# Teensy3_based_M_M_board_Autorouted.net
KiCad netlist of a schematic drawn in EAGLE
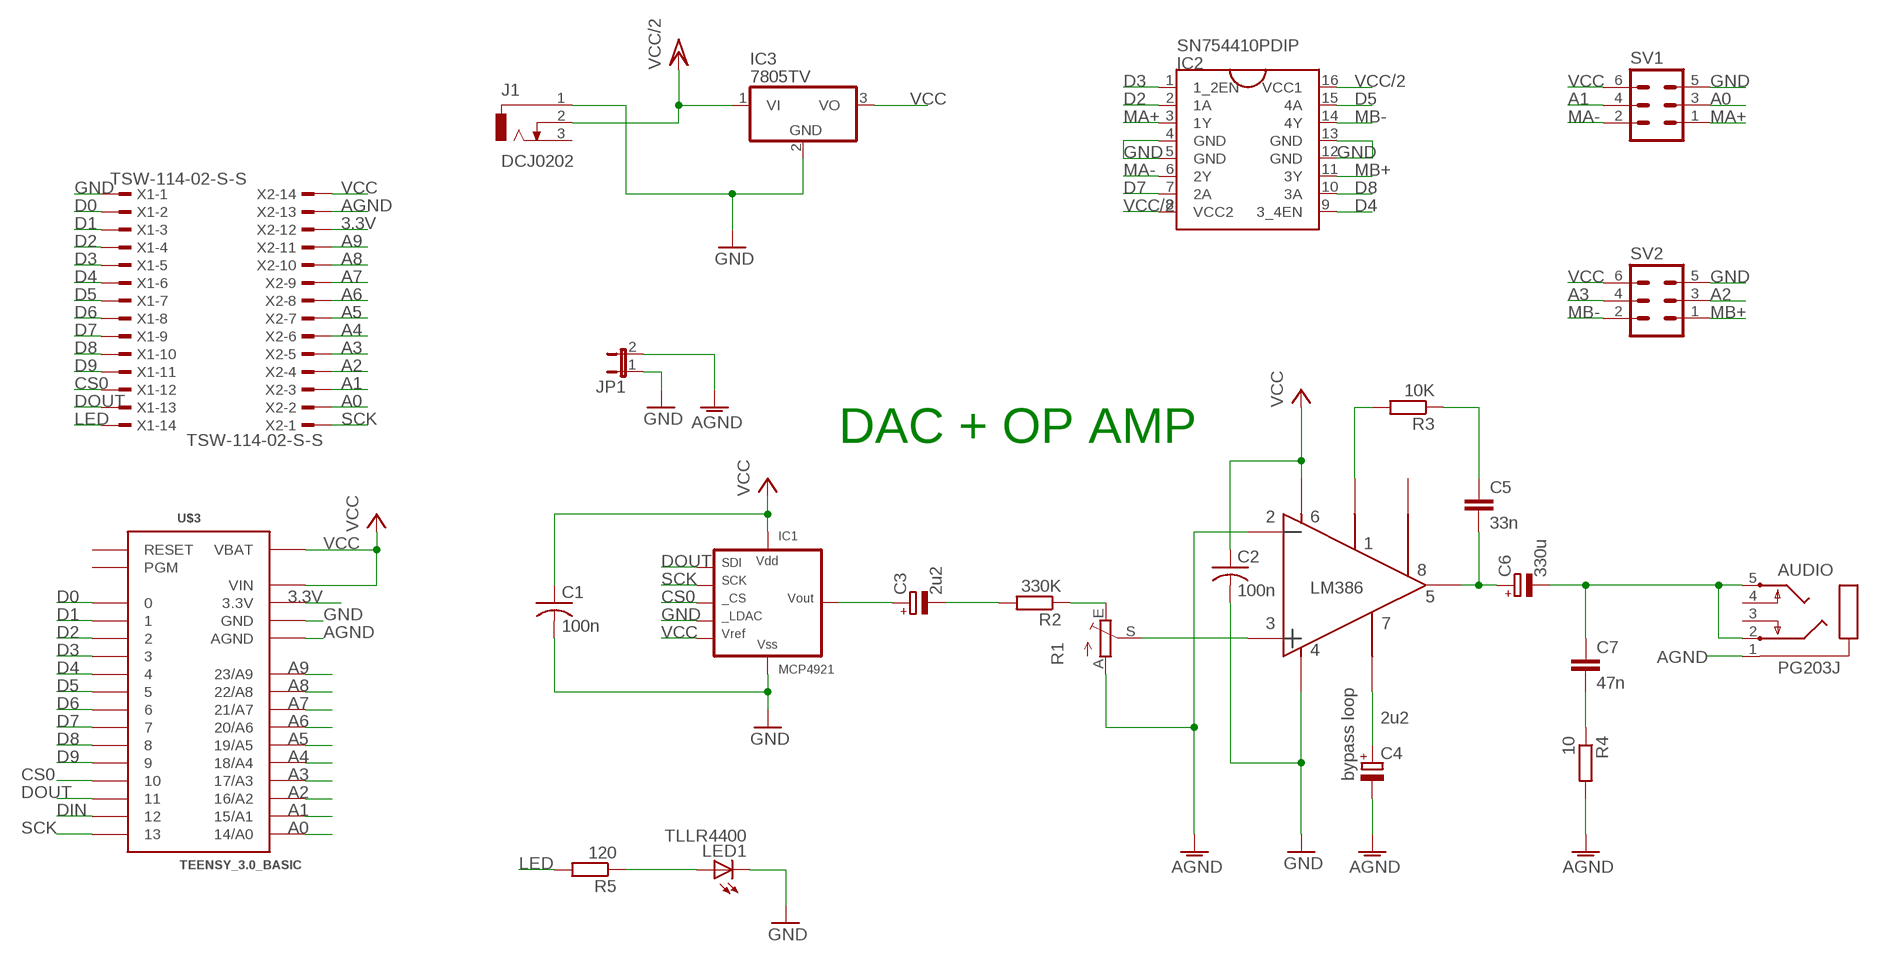
[diagram p0: schematic, sheet 1]

(export (version "E")
  (design (tool "Eeschema 10.0.6"))
  (components
    (comp (ref "AUDIO")
      (value "PG203J")
      (footprint "eagle-import:PG203J")
      (libsource (lib "eagle-import") (part "PG203J"))
    )
    (comp (ref "C1")
      (value "100n")
      (footprint "eagle-import:C050-035X075")
      (libsource (lib "eagle-import") (part "C-US050-035X075"))
    )
    (comp (ref "C2")
      (value "100n")
      (footprint "eagle-import:C050-035X075")
      (libsource (lib "eagle-import") (part "C-US050-035X075"))
    )
    (comp (ref "C3")
      (value "2u2")
      (footprint "eagle-import:E2-5")
      (libsource (lib "eagle-import") (part "CPOL-EUE2-5"))
    )
    (comp (ref "C4")
      (value "2u2")
      (footprint "eagle-import:E2-5")
      (libsource (lib "eagle-import") (part "CPOL-EUE2-5"))
    )
    (comp (ref "C5")
      (value "33n")
      (footprint "eagle-import:C050-024X044")
      (libsource (lib "eagle-import") (part "C-EU050-024X044"))
    )
    (comp (ref "C6")
      (value "330u")
      (footprint "eagle-import:E2,5-7")
      (libsource (lib "eagle-import") (part "CPOL-EUE2.5-7"))
    )
    (comp (ref "C7")
      (value "47n")
      (footprint "eagle-import:C050-024X044")
      (libsource (lib "eagle-import") (part "C-EU050-024X044"))
    )
    (comp (ref "IC1")
      (value "MCP4921")
      (footprint "eagle-import:DIL8")
      (libsource (lib "eagle-import") (part "MCP4921P"))
    )
    (comp (ref "IC2")
      (value "SN754410PDIP")
      (footprint "eagle-import:DIL16")
      (libsource (lib "eagle-import") (part "SN754410PDIP"))
    )
    (comp (ref "IC3")
      (value "7805TV")
      (footprint "eagle-import:TO220V")
      (libsource (lib "eagle-import") (part "78TV05"))
    )
    (comp (ref "J1")
      (value "DCJ0202")
      (footprint "eagle-import:DCJ0202")
      (libsource (lib "eagle-import") (part "DCJ0202"))
    )
    (comp (ref "JP1")
      (value "JP1E")
      (footprint "eagle-import:JP1")
      (libsource (lib "eagle-import") (part "JP1E"))
    )
    (comp (ref "LED1")
      (value "TLLR4400")
      (footprint "eagle-import:LED3MM")
      (fields (field (name "MF") "VISHAY SEMICONDUCTOR"))
      (libsource (lib "eagle-import") (part "TLLR4400"))
    )
    (comp (ref "R1")
      (value "TRIM_EU-CA9V")
      (footprint "eagle-import:CA9V")
      (libsource (lib "eagle-import") (part "TRIM_EU-CA9V"))
    )
    (comp (ref "R2")
      (value "330K")
      (footprint "eagle-import:0207_10")
      (libsource (lib "eagle-import") (part "R-EU_0207/10"))
    )
    (comp (ref "R3")
      (value "10K")
      (footprint "eagle-import:0207_10")
      (libsource (lib "eagle-import") (part "R-EU_0207/10"))
    )
    (comp (ref "R4")
      (value "10")
      (footprint "eagle-import:0207_10")
      (libsource (lib "eagle-import") (part "R-EU_0207/10"))
    )
    (comp (ref "R5")
      (value "120")
      (footprint "eagle-import:0207_10")
      (libsource (lib "eagle-import") (part "R-EU_0207/10"))
    )
    (comp (ref "SV1")
      (value "ML6")
      (footprint "eagle-import:ML6")
      (libsource (lib "eagle-import") (part "ML6"))
    )
    (comp (ref "SV2")
      (value "ML6")
      (footprint "eagle-import:ML6")
      (libsource (lib "eagle-import") (part "ML6"))
    )
    (comp (ref "U$2")
      (value "LM386")
      (footprint "eagle-import:LM386")
      (libsource (lib "eagle-import") (part "LM386OA"))
    )
    (comp (ref "U$3")
      (value "TEENSY_3.0_BASIC")
      (footprint "eagle-import:TEENSY_3.0_BASIC")
      (libsource (lib "eagle-import") (part "TEENSY_3.0_BASIC"))
    )
    (comp (ref "X1")
      (value "TSW-114-02-S-S")
      (footprint "eagle-import:TSW-114-02-S-S")
      (libsource (lib "eagle-import") (part "TSW-114-02-S-S"))
    )
    (comp (ref "X2")
      (value "TSW-114-02-S-S")
      (footprint "eagle-import:TSW-114-02-S-S")
      (libsource (lib "eagle-import") (part "TSW-114-02-S-S"))
    )
  )
  (nets
    (net (code "1") (name "/3.3V") (class "Default")
      (node (ref "U$3") (pin "3.3V") (pinfunction "3.3V_3.3V") (pintype "power_in"))
      (node (ref "U$3") (pin "3.3V1") (pinfunction "3.3V_3.3V1") (pintype "power_in"))
      (node (ref "X2") (pin "12") (pinfunction "1_12") (pintype "passive"))
    )
    (net (code "2") (name "/A0") (class "Default")
      (node (ref "SV1") (pin "3") (pinfunction "3_3") (pintype "passive"))
      (node (ref "U$3") (pin "14/A0") (pinfunction "14/A0_14/A0") (pintype "bidirectional"))
      (node (ref "X2") (pin "2") (pinfunction "1_2") (pintype "passive"))
    )
    (net (code "3") (name "/A1") (class "Default")
      (node (ref "SV1") (pin "4") (pinfunction "4_4") (pintype "passive"))
      (node (ref "U$3") (pin "15/A1") (pinfunction "15/A1_15/A1") (pintype "bidirectional"))
      (node (ref "X2") (pin "3") (pinfunction "1_3") (pintype "passive"))
    )
    (net (code "4") (name "/A2") (class "Default")
      (node (ref "SV2") (pin "3") (pinfunction "3_3") (pintype "passive"))
      (node (ref "U$3") (pin "16/A2") (pinfunction "16/A2_16/A2") (pintype "bidirectional"))
      (node (ref "X2") (pin "4") (pinfunction "1_4") (pintype "passive"))
    )
    (net (code "5") (name "/A3") (class "Default")
      (node (ref "SV2") (pin "4") (pinfunction "4_4") (pintype "passive"))
      (node (ref "U$3") (pin "17/A3") (pinfunction "17/A3_17/A3") (pintype "bidirectional"))
      (node (ref "X2") (pin "5") (pinfunction "1_5") (pintype "passive"))
    )
    (net (code "6") (name "/A4") (class "Default")
      (node (ref "U$3") (pin "18/A4") (pinfunction "18/A4_18/A4") (pintype "bidirectional"))
      (node (ref "X2") (pin "6") (pinfunction "1_6") (pintype "passive"))
    )
    (net (code "7") (name "/A5") (class "Default")
      (node (ref "U$3") (pin "19/A5") (pinfunction "19/A5_19/A5") (pintype "bidirectional"))
      (node (ref "X2") (pin "7") (pinfunction "1_7") (pintype "passive"))
    )
    (net (code "8") (name "/A6") (class "Default")
      (node (ref "U$3") (pin "20/A6") (pinfunction "20/A6_20/A6") (pintype "bidirectional"))
      (node (ref "X2") (pin "8") (pinfunction "1_8") (pintype "passive"))
    )
    (net (code "9") (name "/A7") (class "Default")
      (node (ref "U$3") (pin "21/A7") (pinfunction "21/A7_21/A7") (pintype "bidirectional"))
      (node (ref "X2") (pin "9") (pinfunction "1_9") (pintype "passive"))
    )
    (net (code "10") (name "/A8") (class "Default")
      (node (ref "U$3") (pin "22/A8") (pinfunction "22/A8_22/A8") (pintype "bidirectional"))
      (node (ref "X2") (pin "10") (pinfunction "1_10") (pintype "passive"))
    )
    (net (code "11") (name "/A9") (class "Default")
      (node (ref "U$3") (pin "23/A9") (pinfunction "23/A9_23/A9") (pintype "bidirectional"))
      (node (ref "X2") (pin "11") (pinfunction "1_11") (pintype "passive"))
    )
    (net (code "12") (name "/CS0") (class "Default")
      (node (ref "IC1") (pin "2") (pinfunction "CS_2") (pintype "input"))
      (node (ref "U$3") (pin "10") (pinfunction "10_10") (pintype "bidirectional"))
      (node (ref "X1") (pin "12") (pinfunction "1_12") (pintype "passive"))
    )
    (net (code "13") (name "/D0") (class "Default")
      (node (ref "U$3") (pin "0") (pinfunction "0_0") (pintype "bidirectional"))
      (node (ref "X1") (pin "2") (pinfunction "1_2") (pintype "passive"))
    )
    (net (code "14") (name "/D1") (class "Default")
      (node (ref "U$3") (pin "1") (pinfunction "1_1") (pintype "bidirectional"))
      (node (ref "X1") (pin "3") (pinfunction "1_3") (pintype "passive"))
    )
    (net (code "15") (name "/D2") (class "Default")
      (node (ref "IC2") (pin "2") (pinfunction "1A_2") (pintype "bidirectional"))
      (node (ref "U$3") (pin "2") (pinfunction "2_2") (pintype "bidirectional"))
      (node (ref "X1") (pin "4") (pinfunction "1_4") (pintype "passive"))
    )
    (net (code "16") (name "/D3") (class "Default")
      (node (ref "IC2") (pin "1") (pinfunction "1_2EN_1") (pintype "bidirectional"))
      (node (ref "U$3") (pin "3") (pinfunction "3_3") (pintype "bidirectional"))
      (node (ref "X1") (pin "5") (pinfunction "1_5") (pintype "passive"))
    )
    (net (code "17") (name "/D4") (class "Default")
      (node (ref "IC2") (pin "9") (pinfunction "3_4EN_9") (pintype "bidirectional"))
      (node (ref "U$3") (pin "4") (pinfunction "4_4") (pintype "bidirectional"))
      (node (ref "X1") (pin "6") (pinfunction "1_6") (pintype "passive"))
    )
    (net (code "18") (name "/D5") (class "Default")
      (node (ref "IC2") (pin "15") (pinfunction "4A_15") (pintype "bidirectional"))
      (node (ref "U$3") (pin "5") (pinfunction "5_5") (pintype "bidirectional"))
      (node (ref "X1") (pin "7") (pinfunction "1_7") (pintype "passive"))
    )
    (net (code "19") (name "/D6") (class "Default")
      (node (ref "U$3") (pin "6") (pinfunction "6_6") (pintype "bidirectional"))
      (node (ref "X1") (pin "8") (pinfunction "1_8") (pintype "passive"))
    )
    (net (code "20") (name "/D7") (class "Default")
      (node (ref "IC2") (pin "7") (pinfunction "2A_7") (pintype "bidirectional"))
      (node (ref "U$3") (pin "7") (pinfunction "7_7") (pintype "bidirectional"))
      (node (ref "X1") (pin "9") (pinfunction "1_9") (pintype "passive"))
    )
    (net (code "21") (name "/D8") (class "Default")
      (node (ref "IC2") (pin "10") (pinfunction "3A_10") (pintype "bidirectional"))
      (node (ref "U$3") (pin "8") (pinfunction "8_8") (pintype "bidirectional"))
      (node (ref "X1") (pin "10") (pinfunction "1_10") (pintype "passive"))
    )
    (net (code "22") (name "/D9") (class "Default")
      (node (ref "U$3") (pin "9") (pinfunction "9_9") (pintype "bidirectional"))
      (node (ref "X1") (pin "11") (pinfunction "1_11") (pintype "passive"))
    )
    (net (code "23") (name "/DIN") (class "Default")
      (node (ref "U$3") (pin "12") (pinfunction "12_12") (pintype "bidirectional"))
    )
    (net (code "24") (name "/DOUT") (class "Default")
      (node (ref "IC1") (pin "4") (pinfunction "SDI_4") (pintype "input"))
      (node (ref "U$3") (pin "11") (pinfunction "11_11") (pintype "bidirectional"))
      (node (ref "X1") (pin "13") (pinfunction "1_13") (pintype "passive"))
    )
    (net (code "25") (name "/LED") (class "Default")
      (node (ref "R5") (pin "2") (pinfunction "2_2") (pintype "passive"))
      (node (ref "X1") (pin "14") (pinfunction "1_14") (pintype "passive"))
    )
    (net (code "26") (name "/MA+") (class "Default")
      (node (ref "IC2") (pin "3") (pinfunction "1Y_3") (pintype "bidirectional"))
      (node (ref "SV1") (pin "1") (pinfunction "1_1") (pintype "passive"))
    )
    (net (code "27") (name "/MA-") (class "Default")
      (node (ref "IC2") (pin "6") (pinfunction "2Y_6") (pintype "bidirectional"))
      (node (ref "SV1") (pin "2") (pinfunction "2_2") (pintype "passive"))
    )
    (net (code "28") (name "/MB+") (class "Default")
      (node (ref "IC2") (pin "11") (pinfunction "3Y_11") (pintype "bidirectional"))
      (node (ref "SV2") (pin "1") (pinfunction "1_1") (pintype "passive"))
    )
    (net (code "29") (name "/MB-") (class "Default")
      (node (ref "IC2") (pin "14") (pinfunction "4Y_14") (pintype "bidirectional"))
      (node (ref "SV2") (pin "2") (pinfunction "2_2") (pintype "passive"))
    )
    (net (code "30") (name "/SCK") (class "Default")
      (node (ref "IC1") (pin "3") (pinfunction "SCK_3") (pintype "input"))
      (node (ref "U$3") (pin "13") (pinfunction "13_13") (pintype "bidirectional"))
      (node (ref "X2") (pin "1") (pinfunction "1_1") (pintype "passive"))
    )
    (net (code "31") (name "AGND") (class "Default")
      (node (ref "AUDIO") (pin "1") (pinfunction "1_1") (pintype "passive"))
      (node (ref "C4") (pin "-") (pinfunction "-_-") (pintype "passive"))
      (node (ref "JP1") (pin "2") (pinfunction "2_2") (pintype "passive"))
      (node (ref "R1") (pin "A") (pinfunction "A_A") (pintype "passive"))
      (node (ref "R4") (pin "2") (pinfunction "2_2") (pintype "passive"))
      (node (ref "U$2") (pin "2") (pinfunction "P$2_2") (pintype "bidirectional"))
      (node (ref "U$3") (pin "AGND") (pinfunction "AGND_AGND") (pintype "power_in"))
      (node (ref "X2") (pin "13") (pinfunction "1_13") (pintype "passive"))
    )
    (net (code "32") (name "GND") (class "Default")
      (node (ref "C1") (pin "2") (pinfunction "2_2") (pintype "passive"))
      (node (ref "C2") (pin "2") (pinfunction "2_2") (pintype "passive"))
      (node (ref "IC1") (pin "5") (pinfunction "LDAC_5") (pintype "input"))
      (node (ref "IC1") (pin "7") (pinfunction "VSS_7") (pintype "power_in"))
      (node (ref "IC2") (pin "12") (pinfunction "GND_12") (pintype "bidirectional"))
      (node (ref "IC2") (pin "13") (pinfunction "GND_13") (pintype "bidirectional"))
      (node (ref "IC2") (pin "4") (pinfunction "GND_4") (pintype "bidirectional"))
      (node (ref "IC2") (pin "5") (pinfunction "GND_5") (pintype "bidirectional"))
      (node (ref "IC3") (pin "2") (pinfunction "GND_2") (pintype "passive"))
      (node (ref "J1") (pin "1") (pinfunction "1_1") (pintype "passive"))
      (node (ref "JP1") (pin "1") (pinfunction "1_1") (pintype "passive"))
      (node (ref "LED1") (pin "K") (pinfunction "C_K") (pintype "passive"))
      (node (ref "SV1") (pin "5") (pinfunction "5_5") (pintype "passive"))
      (node (ref "SV2") (pin "5") (pinfunction "5_5") (pintype "passive"))
      (node (ref "U$2") (pin "4") (pinfunction "P$4_4") (pintype "bidirectional"))
      (node (ref "U$3") (pin "GND") (pinfunction "GND_GND") (pintype "power_in"))
      (node (ref "U$3") (pin "GND1") (pinfunction "GND_GND1") (pintype "power_in"))
      (node (ref "X1") (pin "1") (pinfunction "1_1") (pintype "passive"))
    )
    (net (code "33") (name "Net-(AUDIO-Pad2)") (class "Default")
      (node (ref "AUDIO") (pin "2") (pinfunction "2_2") (pintype "passive"))
      (node (ref "AUDIO") (pin "5") (pinfunction "5_5") (pintype "passive"))
      (node (ref "C6") (pin "-") (pinfunction "-_-") (pintype "passive"))
      (node (ref "C7") (pin "1") (pinfunction "1_1") (pintype "passive"))
    )
    (net (code "34") (name "Net-(C3-Pad-)") (class "Default")
      (node (ref "C3") (pin "-") (pinfunction "-_-") (pintype "passive"))
      (node (ref "R2") (pin "2") (pinfunction "2_2") (pintype "passive"))
    )
    (net (code "35") (name "Net-(C5-Pad1)") (class "Default")
      (node (ref "C5") (pin "1") (pinfunction "1_1") (pintype "passive"))
      (node (ref "R3") (pin "1") (pinfunction "1_1") (pintype "passive"))
    )
    (net (code "36") (name "Net-(C7-Pad2)") (class "Default")
      (node (ref "C7") (pin "2") (pinfunction "2_2") (pintype "passive"))
      (node (ref "R4") (pin "1") (pinfunction "1_1") (pintype "passive"))
    )
    (net (code "37") (name "Net-(IC1-VOUT)") (class "Default")
      (node (ref "C3") (pin "+") (pinfunction "+_+") (pintype "passive"))
      (node (ref "IC1") (pin "8") (pinfunction "VOUT_8") (pintype "output"))
    )
    (net (code "38") (name "Net-(LED1-PadA)") (class "Default")
      (node (ref "LED1") (pin "A") (pinfunction "A_A") (pintype "passive"))
      (node (ref "R5") (pin "1") (pinfunction "1_1") (pintype "passive"))
    )
    (net (code "39") (name "Net-(R1-PadE)") (class "Default")
      (node (ref "R1") (pin "E") (pinfunction "E_E") (pintype "passive"))
      (node (ref "R2") (pin "1") (pinfunction "1_1") (pintype "passive"))
    )
    (net (code "40") (name "Net-(U$2-P$1)") (class "Default")
      (node (ref "R3") (pin "2") (pinfunction "2_2") (pintype "passive"))
      (node (ref "U$2") (pin "1") (pinfunction "P$1_1") (pintype "bidirectional"))
    )
    (net (code "41") (name "Net-(U$2-P$3)") (class "Default")
      (node (ref "R1") (pin "S") (pinfunction "S_S") (pintype "passive"))
      (node (ref "U$2") (pin "3") (pinfunction "P$3_3") (pintype "bidirectional"))
    )
    (net (code "42") (name "Net-(U$2-P$5)") (class "Default")
      (node (ref "C5") (pin "2") (pinfunction "2_2") (pintype "passive"))
      (node (ref "C6") (pin "+") (pinfunction "+_+") (pintype "passive"))
      (node (ref "U$2") (pin "5") (pinfunction "P$5_5") (pintype "bidirectional"))
    )
    (net (code "43") (name "Net-(U$2-P$7)") (class "Default")
      (node (ref "C4") (pin "+") (pinfunction "+_+") (pintype "passive"))
      (node (ref "U$2") (pin "7") (pinfunction "P$7_7") (pintype "bidirectional"))
    )
    (net (code "44") (name "VCC") (class "Default")
      (node (ref "C1") (pin "1") (pinfunction "1_1") (pintype "passive"))
      (node (ref "C2") (pin "1") (pinfunction "1_1") (pintype "passive"))
      (node (ref "IC1") (pin "1") (pinfunction "VDD_1") (pintype "power_in"))
      (node (ref "IC1") (pin "6") (pinfunction "VREF_6") (pintype "input"))
      (node (ref "IC3") (pin "3") (pinfunction "VO_3") (pintype "passive"))
      (node (ref "SV1") (pin "6") (pinfunction "6_6") (pintype "passive"))
      (node (ref "SV2") (pin "6") (pinfunction "6_6") (pintype "passive"))
      (node (ref "U$2") (pin "6") (pinfunction "P$6_6") (pintype "bidirectional"))
      (node (ref "U$3") (pin "VBAT") (pinfunction "VBAT_VBAT") (pintype "power_in"))
      (node (ref "U$3") (pin "VIN") (pinfunction "VIN_VIN") (pintype "power_in"))
      (node (ref "X2") (pin "14") (pinfunction "1_14") (pintype "passive"))
    )
    (net (code "45") (name "VCC{slash}2") (class "Default")
      (node (ref "IC2") (pin "16") (pinfunction "VCC1_16") (pintype "bidirectional"))
      (node (ref "IC2") (pin "8") (pinfunction "VCC2_8") (pintype "bidirectional"))
      (node (ref "IC3") (pin "1") (pinfunction "VI_1") (pintype "input"))
      (node (ref "J1") (pin "2") (pinfunction "2_2") (pintype "passive"))
    )
    (net (code "46") (name "unconnected-(AUDIO-Pad3)") (class "Default")
      (node (ref "AUDIO") (pin "3") (pinfunction "3_3") (pintype "passive"))
    )
    (net (code "47") (name "unconnected-(AUDIO-Pad4)") (class "Default")
      (node (ref "AUDIO") (pin "4") (pinfunction "4_4") (pintype "passive"))
    )
    (net (code "48") (name "unconnected-(J1-Pad3)") (class "Default")
      (node (ref "J1") (pin "3") (pinfunction "3_3") (pintype "passive"))
    )
    (net (code "49") (name "unconnected-(U$2-P$8-Pad8)") (class "Default")
      (node (ref "U$2") (pin "8") (pinfunction "P$8_8") (pintype "bidirectional"))
    )
    (net (code "50") (name "unconnected-(U$3-PadPGM)") (class "Default")
      (node (ref "U$3") (pin "PGM") (pinfunction "PGM_PGM") (pintype "bidirectional"))
    )
    (net (code "51") (name "unconnected-(U$3-PadRESET)") (class "Default")
      (node (ref "U$3") (pin "RESET") (pinfunction "RESET_RESET") (pintype "bidirectional"))
    )
  )
)
